# active_softstart_mig.net
KiCad netlist of a schematic drawn in EAGLE
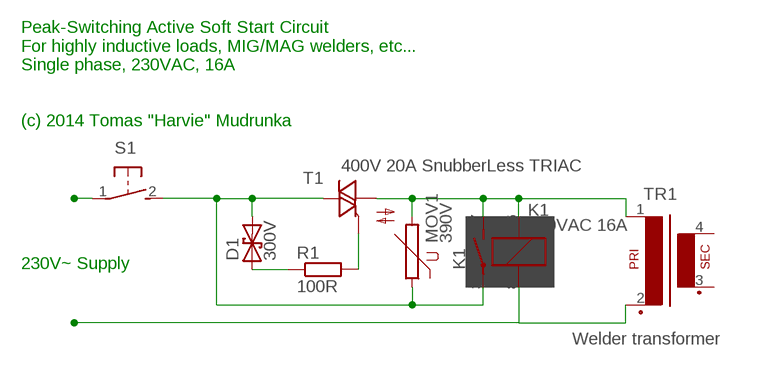
[diagram p0: schematic, sheet 1]

(export (version "E")
  (design (tool "Eeschema 10.0.6"))
  (components
    (comp (ref "D1")
      (value "300V")
      (footprint "eagle-import:CB417-15")
      (libsource (lib "eagle-import") (part "P6KEXXC"))
    )
    (comp (ref "K1")
      (value "230VAC 16A")
      (footprint "eagle-import:CB1")
      (fields (field (name "MF") "AROMAT/ MATSUSHITA") (field (name "MPN") "CB1A-P-12V"))
      (libsource (lib "eagle-import") (part "CB1A-P-12V"))
    )
    (comp (ref "MOV1")
      (value "390V")
      (footprint "eagle-import:P592")
      (libsource (lib "eagle-import") (part "P592"))
    )
    (comp (ref "R1")
      (value "100R")
      (footprint "eagle-import:0204V")
      (libsource (lib "eagle-import") (part "R-EU_0204/2V"))
    )
    (comp (ref "S1")
      (value "31-XX")
      (footprint "eagle-import:B3F-31XX")
      (fields (field (name "MPN") "B3F-3100"))
      (libsource (lib "eagle-import") (part "31-XX"))
    )
    (comp (ref "T1")
      (value "400V 20A SnubberLess TRIAC")
      (footprint "eagle-import:TOP3S-1")
      (libsource (lib "eagle-import") (part "BTA26-V"))
    )
    (comp (ref "TR1")
      (value "Welder transformer")
      (footprint "eagle-import:VR22-1")
      (libsource (lib "eagle-import") (part "VR2230-1"))
    )
  )
  (nets
    (net (code "1") (name "Net-(D1-1)") (class "Default")
      (node (ref "D1") (pin "A") (pinfunction "1_A") (pintype "passive"))
      (node (ref "R1") (pin "1") (pinfunction "1_1") (pintype "passive"))
    )
    (net (code "2") (name "Net-(D1-2)") (class "Default")
      (node (ref "D1") (pin "C") (pinfunction "2_C") (pintype "passive"))
      (node (ref "K1") (pin "30") (pinfunction "P_30") (pintype "passive"))
      (node (ref "MOV1") (pin "1") (pinfunction "1_1") (pintype "passive"))
      (node (ref "S1") (pin "2") (pinfunction "S_2") (pintype "passive"))
      (node (ref "T1") (pin "A2") (pinfunction "A2_A2") (pintype "passive"))
    )
    (net (code "3") (name "Net-(K1A-1)") (class "Default")
      (node (ref "K1") (pin "86") (pinfunction "1_86") (pintype "passive"))
      (node (ref "K1") (pin "87") (pinfunction "S_87") (pintype "passive"))
      (node (ref "MOV1") (pin "2") (pinfunction "2_2") (pintype "passive"))
      (node (ref "T1") (pin "A1") (pinfunction "A1_A1") (pintype "passive"))
      (node (ref "TR1") (pin "1") (pinfunction "P1_1") (pintype "passive"))
    )
    (net (code "4") (name "Net-(K1A-2)") (class "Default")
      (node (ref "K1") (pin "85") (pinfunction "2_85") (pintype "passive"))
      (node (ref "TR1") (pin "2") (pinfunction "P2_2") (pintype "passive"))
    )
    (net (code "5") (name "Net-(R1-Pad2)") (class "Default")
      (node (ref "R1") (pin "2") (pinfunction "2_2") (pintype "passive"))
      (node (ref "T1") (pin "G") (pinfunction "G_G") (pintype "passive"))
    )
    (net (code "6") (name "unconnected-(S1-P-Pad1)") (class "Default")
      (node (ref "S1") (pin "1") (pinfunction "P_1") (pintype "passive"))
    )
    (net (code "7") (name "unconnected-(TR1-S3-Pad3)") (class "Default")
      (node (ref "TR1") (pin "3") (pinfunction "S3_3") (pintype "passive"))
    )
    (net (code "8") (name "unconnected-(TR1-S4-Pad4)") (class "Default")
      (node (ref "TR1") (pin "4") (pinfunction "S4_4") (pintype "passive"))
    )
  )
)
